# piHatJoystick.net
KiCad netlist of a schematic drawn in EAGLE
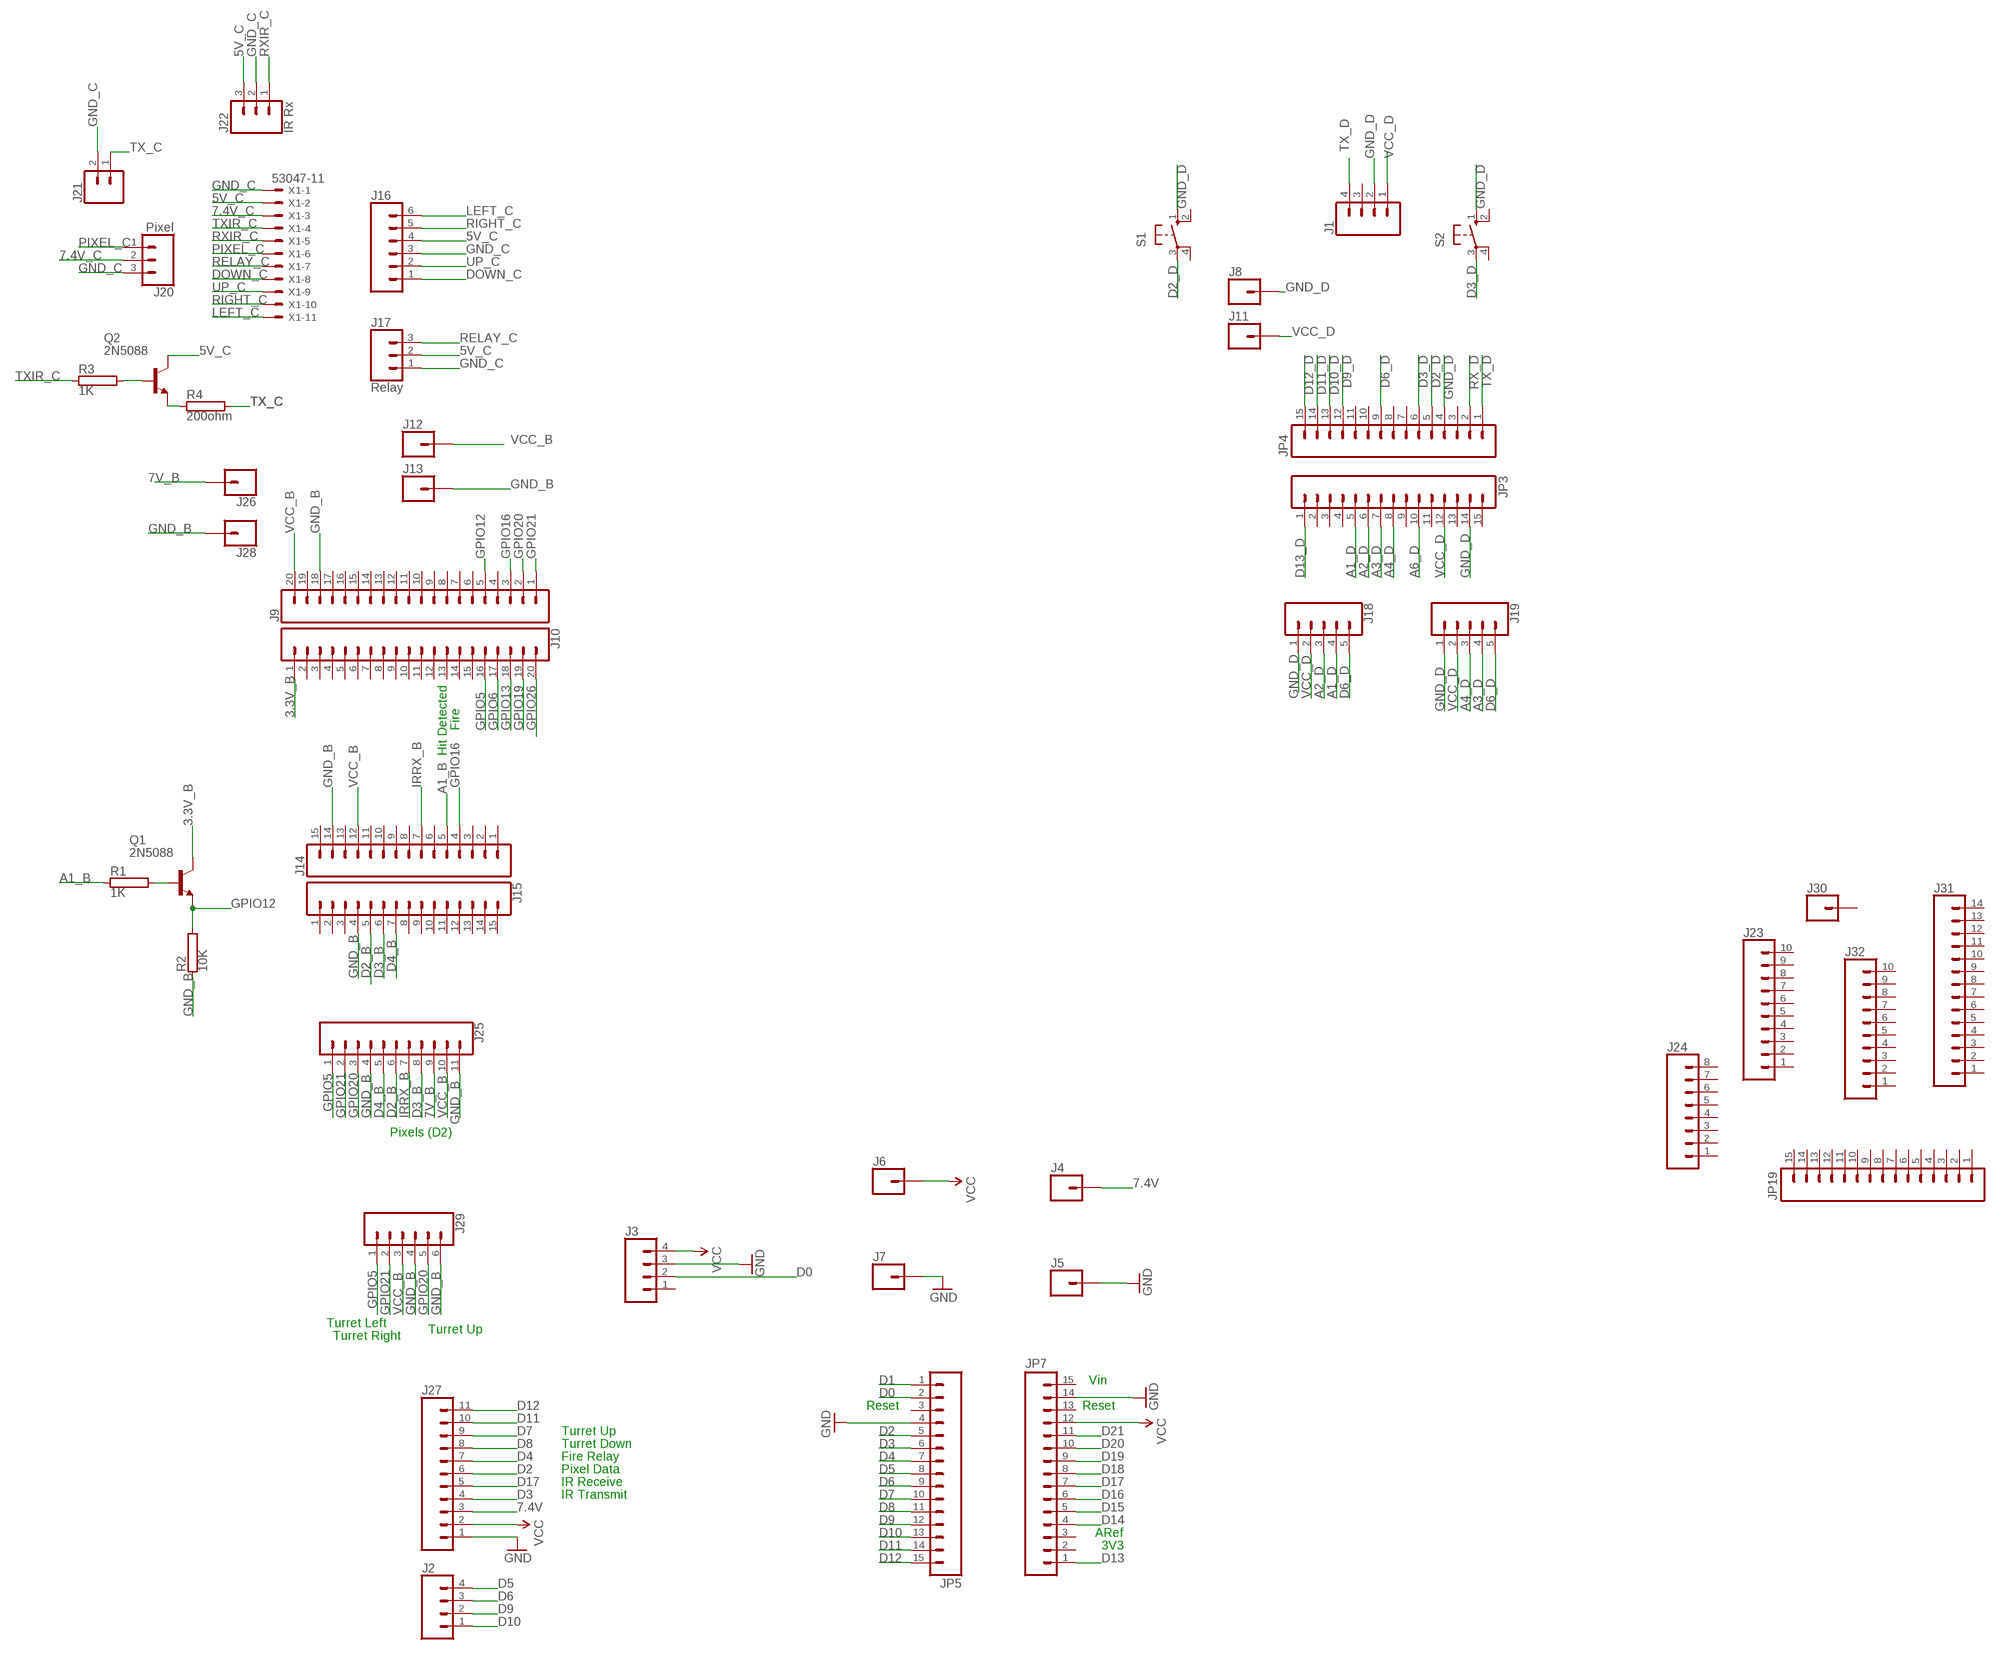
[diagram p0: schematic, sheet 1]

(export (version "E")
  (design (tool "Eeschema 10.0.6"))
  (components
    (comp (ref "J1")
      (value "CONN_04")
      (footprint "eagle-import:1X04")
      (libsource (lib "eagle-import") (part "SparkFun-Connectors_513_CONN_04"))
    )
    (comp (ref "J2")
      (value "CONN_04")
      (footprint "eagle-import:1X04")
      (libsource (lib "eagle-import") (part "CONN_04"))
    )
    (comp (ref "J3")
      (value "CONN_04")
      (footprint "eagle-import:1X04")
      (libsource (lib "eagle-import") (part "CONN_04"))
    )
    (comp (ref "J4")
      (value "CONN_01")
      (footprint "eagle-import:1X01")
      (libsource (lib "eagle-import") (part "SparkFun-Connectors_513_CONN_01"))
    )
    (comp (ref "J5")
      (value "CONN_01")
      (footprint "eagle-import:1X01")
      (libsource (lib "eagle-import") (part "SparkFun-Connectors_513_CONN_01"))
    )
    (comp (ref "J6")
      (value "CONN_01")
      (footprint "eagle-import:1X01")
      (libsource (lib "eagle-import") (part "SparkFun-Connectors_513_CONN_01"))
    )
    (comp (ref "J7")
      (value "CONN_01")
      (footprint "eagle-import:1X01")
      (libsource (lib "eagle-import") (part "SparkFun-Connectors_513_CONN_01"))
    )
    (comp (ref "J8")
      (value "CONN_01")
      (footprint "eagle-import:1X01")
      (libsource (lib "eagle-import") (part "SparkFun-Connectors_513_CONN_01"))
    )
    (comp (ref "J9")
      (value "CONN_20")
      (footprint "eagle-import:1X20")
      (libsource (lib "eagle-import") (part "CONN_20"))
    )
    (comp (ref "J10")
      (value "CONN_20")
      (footprint "eagle-import:1X20")
      (libsource (lib "eagle-import") (part "CONN_20"))
    )
    (comp (ref "J11")
      (value "CONN_01")
      (footprint "eagle-import:1X01")
      (libsource (lib "eagle-import") (part "SparkFun-Connectors_513_CONN_01"))
    )
    (comp (ref "J12")
      (value "CONN_01")
      (footprint "eagle-import:1X01")
      (libsource (lib "eagle-import") (part "CONN_01"))
    )
    (comp (ref "J13")
      (value "CONN_01")
      (footprint "eagle-import:1X01")
      (libsource (lib "eagle-import") (part "CONN_01"))
    )
    (comp (ref "J14")
      (value "CONN_15")
      (footprint "eagle-import:1X15")
      (libsource (lib "eagle-import") (part "CONN_15"))
    )
    (comp (ref "J15")
      (value "CONN_15")
      (footprint "eagle-import:1X15")
      (libsource (lib "eagle-import") (part "CONN_15"))
    )
    (comp (ref "J16")
      (value "CONN_06NO_SILK_FEMALE_PTH")
      (footprint "eagle-import:1X06_NO_SILK")
      (libsource (lib "eagle-import") (part "CONN_06NO_SILK_FEMALE_PTH"))
    )
    (comp (ref "J17")
      (value "Relay")
      (footprint "eagle-import:1X03")
      (libsource (lib "eagle-import") (part "CONN_03"))
    )
    (comp (ref "J18")
      (value "CONN_05")
      (footprint "eagle-import:1X05")
      (libsource (lib "eagle-import") (part "CONN_05"))
    )
    (comp (ref "J19")
      (value "CONN_05")
      (footprint "eagle-import:1X05")
      (libsource (lib "eagle-import") (part "CONN_05"))
    )
    (comp (ref "J20")
      (value "Pixel")
      (footprint "eagle-import:1X03")
      (libsource (lib "eagle-import") (part "CONN_03"))
    )
    (comp (ref "J21")
      (value "CONN_02")
      (footprint "eagle-import:1X02")
      (libsource (lib "eagle-import") (part "CONN_02"))
    )
    (comp (ref "J22")
      (value "IR Rx")
      (footprint "eagle-import:1X03")
      (libsource (lib "eagle-import") (part "CONN_03"))
    )
    (comp (ref "J23")
      (value "CONN_10\"")
      (footprint "eagle-import:1X10")
      (libsource (lib "eagle-import") (part "CONN_10{dblquote}"))
    )
    (comp (ref "J24")
      (value "CONN_08\"")
      (footprint "eagle-import:1X08")
      (libsource (lib "eagle-import") (part "CONN_08{dblquote}"))
    )
    (comp (ref "J25")
      (value "CONN_11")
      (footprint "eagle-import:1X11")
      (libsource (lib "eagle-import") (part "CONN_11"))
    )
    (comp (ref "J26")
      (value "CONN_01")
      (footprint "eagle-import:1X01")
      (libsource (lib "eagle-import") (part "CONN_01"))
    )
    (comp (ref "J27")
      (value "CONN_11")
      (footprint "eagle-import:1X11")
      (libsource (lib "eagle-import") (part "SparkFun-Connectors_513_CONN_11"))
    )
    (comp (ref "J28")
      (value "CONN_01")
      (footprint "eagle-import:1X01")
      (libsource (lib "eagle-import") (part "CONN_01"))
    )
    (comp (ref "J29")
      (value "CONN_06NO_SILK_FEMALE_PTH")
      (footprint "eagle-import:1X06_NO_SILK")
      (libsource (lib "eagle-import") (part "CONN_06NO_SILK_FEMALE_PTH"))
    )
    (comp (ref "J30")
      (value "CONN_01")
      (footprint "eagle-import:1X01")
      (libsource (lib "eagle-import") (part "SparkFun-Connectors_513_CONN_01"))
    )
    (comp (ref "J31")
      (value "CONN_14")
      (footprint "eagle-import:1X14")
      (libsource (lib "eagle-import") (part "CONN_14"))
    )
    (comp (ref "J32")
      (value "CONN_10\"")
      (footprint "eagle-import:1X10")
      (libsource (lib "eagle-import") (part "CONN_10{dblquote}"))
    )
    (comp (ref "JP3")
      (value "M15")
      (footprint "eagle-import:1X15@1")
      (libsource (lib "eagle-import") (part "M15"))
    )
    (comp (ref "JP4")
      (value "M15")
      (footprint "eagle-import:1X15@1")
      (libsource (lib "eagle-import") (part "M15"))
    )
    (comp (ref "JP5")
      (value "M15")
      (footprint "eagle-import:1X15@1")
      (libsource (lib "eagle-import") (part "M15"))
    )
    (comp (ref "JP7")
      (value "M15")
      (footprint "eagle-import:1X15@1")
      (libsource (lib "eagle-import") (part "M15"))
    )
    (comp (ref "JP19")
      (value "M15")
      (footprint "eagle-import:1X15@1")
      (libsource (lib "eagle-import") (part "M15"))
    )
    (comp (ref "Q1")
      (value "2N5088")
      (footprint "eagle-import:TO92")
      (libsource (lib "eagle-import") (part "2N5088"))
    )
    (comp (ref "Q2")
      (value "2N5088")
      (footprint "eagle-import:TO92")
      (libsource (lib "eagle-import") (part "2N5088"))
    )
    (comp (ref "R1")
      (value "1K")
      (footprint "eagle-import:CA0001")
      (libsource (lib "eagle-import") (part "RCA0001"))
    )
    (comp (ref "R2")
      (value "10K")
      (footprint "eagle-import:CA0001")
      (libsource (lib "eagle-import") (part "RCA0001"))
    )
    (comp (ref "R3")
      (value "1K")
      (footprint "eagle-import:CA0001")
      (libsource (lib "eagle-import") (part "RCA0001"))
    )
    (comp (ref "R4")
      (value "200ohm")
      (footprint "eagle-import:CA0001")
      (libsource (lib "eagle-import") (part "RCA0001"))
    )
    (comp (ref "S1")
      (value "40-XX")
      (footprint "eagle-import:B3F-40XX")
      (fields (field (name "MF") "OMRON COMPONENTS USA") (field (name "MPN") "B3F-4000"))
      (libsource (lib "eagle-import") (part "40-XX"))
    )
    (comp (ref "S2")
      (value "40-XX")
      (footprint "eagle-import:B3F-40XX")
      (fields (field (name "MF") "OMRON COMPONENTS USA") (field (name "MPN") "B3F-4000"))
      (libsource (lib "eagle-import") (part "40-XX"))
    )
    (comp (ref "X1")
      (value "53047-11")
      (footprint "eagle-import:53047-11")
      (fields (field (name "MF") "WALDOM/MOLEX") (field (name "MPN") "53047-1110"))
      (libsource (lib "eagle-import") (part "53?-11047"))
    )
  )
  (nets
    (net (code "1") (name "/3.3V_B") (class "Default")
      (node (ref "J10") (pin "1") (pinfunction "1_1") (pintype "passive"))
      (node (ref "Q1") (pin "1") (pinfunction "C_1") (pintype "passive"))
    )
    (net (code "2") (name "/5V_C") (class "Default")
      (node (ref "J16") (pin "4") (pinfunction "4_4") (pintype "passive"))
      (node (ref "J17") (pin "2") (pinfunction "2_2") (pintype "passive"))
      (node (ref "J22") (pin "3") (pinfunction "3_3") (pintype "passive"))
      (node (ref "Q2") (pin "1") (pinfunction "C_1") (pintype "passive"))
      (node (ref "X1") (pin "2") (pinfunction "S_2") (pintype "passive"))
    )
    (net (code "3") (name "/7.4V") (class "Default")
      (node (ref "J27") (pin "3") (pinfunction "3_3") (pintype "passive"))
      (node (ref "J4") (pin "1") (pinfunction "1_1") (pintype "passive"))
    )
    (net (code "4") (name "/7.4V_C") (class "Default")
      (node (ref "J20") (pin "2") (pinfunction "2_2") (pintype "passive"))
      (node (ref "X1") (pin "3") (pinfunction "S_3") (pintype "passive"))
    )
    (net (code "5") (name "/7V_B") (class "Default")
      (node (ref "J25") (pin "9") (pinfunction "9_9") (pintype "passive"))
      (node (ref "J26") (pin "1") (pinfunction "1_1") (pintype "passive"))
    )
    (net (code "6") (name "/A1_B") (class "Default")
      (node (ref "J14") (pin "5") (pinfunction "5_5") (pintype "passive"))
      (node (ref "R1") (pin "1") (pinfunction "1_1") (pintype "passive"))
    )
    (net (code "7") (name "/A1_D") (class "Default")
      (node (ref "J18") (pin "4") (pinfunction "4_4") (pintype "passive"))
      (node (ref "JP3") (pin "5") (pinfunction "5_5") (pintype "passive"))
    )
    (net (code "8") (name "/A2_D") (class "Default")
      (node (ref "J18") (pin "3") (pinfunction "3_3") (pintype "passive"))
      (node (ref "JP3") (pin "6") (pinfunction "6_6") (pintype "passive"))
    )
    (net (code "9") (name "/A3_D") (class "Default")
      (node (ref "J19") (pin "4") (pinfunction "4_4") (pintype "passive"))
      (node (ref "JP3") (pin "7") (pinfunction "7_7") (pintype "passive"))
    )
    (net (code "10") (name "/A4_D") (class "Default")
      (node (ref "J19") (pin "3") (pinfunction "3_3") (pintype "passive"))
      (node (ref "JP3") (pin "8") (pinfunction "8_8") (pintype "passive"))
    )
    (net (code "11") (name "/A6_D") (class "Default")
      (node (ref "JP3") (pin "10") (pinfunction "10_10") (pintype "passive"))
    )
    (net (code "12") (name "/D0") (class "Default")
      (node (ref "J3") (pin "2") (pinfunction "2_2") (pintype "passive"))
      (node (ref "JP5") (pin "2") (pinfunction "2_2") (pintype "passive"))
    )
    (net (code "13") (name "/D1") (class "Default")
      (node (ref "JP5") (pin "1") (pinfunction "1_1") (pintype "passive"))
    )
    (net (code "14") (name "/D2") (class "Default")
      (node (ref "J27") (pin "6") (pinfunction "6_6") (pintype "passive"))
      (node (ref "JP5") (pin "5") (pinfunction "5_5") (pintype "passive"))
    )
    (net (code "15") (name "/D2_B") (class "Default")
      (node (ref "J15") (pin "5") (pinfunction "5_5") (pintype "passive"))
      (node (ref "J25") (pin "6") (pinfunction "6_6") (pintype "passive"))
    )
    (net (code "16") (name "/D2_D") (class "Default")
      (node (ref "JP4") (pin "5") (pinfunction "5_5") (pintype "passive"))
      (node (ref "S1") (pin "3") (pinfunction "P_3") (pintype "passive"))
    )
    (net (code "17") (name "/D3") (class "Default")
      (node (ref "J27") (pin "4") (pinfunction "4_4") (pintype "passive"))
      (node (ref "JP5") (pin "6") (pinfunction "6_6") (pintype "passive"))
    )
    (net (code "18") (name "/D3_B") (class "Default")
      (node (ref "J15") (pin "6") (pinfunction "6_6") (pintype "passive"))
      (node (ref "J25") (pin "8") (pinfunction "8_8") (pintype "passive"))
    )
    (net (code "19") (name "/D3_D") (class "Default")
      (node (ref "JP4") (pin "6") (pinfunction "6_6") (pintype "passive"))
      (node (ref "S2") (pin "3") (pinfunction "P_3") (pintype "passive"))
    )
    (net (code "20") (name "/D4") (class "Default")
      (node (ref "J27") (pin "7") (pinfunction "7_7") (pintype "passive"))
      (node (ref "JP5") (pin "7") (pinfunction "7_7") (pintype "passive"))
    )
    (net (code "21") (name "/D4_B") (class "Default")
      (node (ref "J15") (pin "7") (pinfunction "7_7") (pintype "passive"))
      (node (ref "J25") (pin "5") (pinfunction "5_5") (pintype "passive"))
    )
    (net (code "22") (name "/D5") (class "Default")
      (node (ref "J2") (pin "4") (pinfunction "4_4") (pintype "passive"))
      (node (ref "JP5") (pin "8") (pinfunction "8_8") (pintype "passive"))
    )
    (net (code "23") (name "/D6") (class "Default")
      (node (ref "J2") (pin "3") (pinfunction "3_3") (pintype "passive"))
      (node (ref "JP5") (pin "9") (pinfunction "9_9") (pintype "passive"))
    )
    (net (code "24") (name "/D6_D") (class "Default")
      (node (ref "J18") (pin "5") (pinfunction "5_5") (pintype "passive"))
      (node (ref "J19") (pin "5") (pinfunction "5_5") (pintype "passive"))
      (node (ref "JP4") (pin "9") (pinfunction "9_9") (pintype "passive"))
    )
    (net (code "25") (name "/D7") (class "Default")
      (node (ref "J27") (pin "9") (pinfunction "9_9") (pintype "passive"))
      (node (ref "JP5") (pin "10") (pinfunction "10_10") (pintype "passive"))
    )
    (net (code "26") (name "/D8") (class "Default")
      (node (ref "J27") (pin "8") (pinfunction "8_8") (pintype "passive"))
      (node (ref "JP5") (pin "11") (pinfunction "11_11") (pintype "passive"))
    )
    (net (code "27") (name "/D9") (class "Default")
      (node (ref "J2") (pin "2") (pinfunction "2_2") (pintype "passive"))
      (node (ref "JP5") (pin "12") (pinfunction "12_12") (pintype "passive"))
    )
    (net (code "28") (name "/D9_D") (class "Default")
      (node (ref "JP4") (pin "12") (pinfunction "12_12") (pintype "passive"))
    )
    (net (code "29") (name "/D10") (class "Default")
      (node (ref "J2") (pin "1") (pinfunction "1_1") (pintype "passive"))
      (node (ref "JP5") (pin "13") (pinfunction "13_13") (pintype "passive"))
    )
    (net (code "30") (name "/D10_D") (class "Default")
      (node (ref "JP4") (pin "13") (pinfunction "13_13") (pintype "passive"))
    )
    (net (code "31") (name "/D11") (class "Default")
      (node (ref "J27") (pin "10") (pinfunction "10_10") (pintype "passive"))
      (node (ref "JP5") (pin "14") (pinfunction "14_14") (pintype "passive"))
    )
    (net (code "32") (name "/D11_D") (class "Default")
      (node (ref "JP4") (pin "14") (pinfunction "14_14") (pintype "passive"))
    )
    (net (code "33") (name "/D12") (class "Default")
      (node (ref "J27") (pin "11") (pinfunction "11_11") (pintype "passive"))
      (node (ref "JP5") (pin "15") (pinfunction "15_15") (pintype "passive"))
    )
    (net (code "34") (name "/D12_D") (class "Default")
      (node (ref "JP4") (pin "15") (pinfunction "15_15") (pintype "passive"))
    )
    (net (code "35") (name "/D13") (class "Default")
      (node (ref "JP7") (pin "1") (pinfunction "1_1") (pintype "passive"))
    )
    (net (code "36") (name "/D13_D") (class "Default")
      (node (ref "JP3") (pin "1") (pinfunction "1_1") (pintype "passive"))
    )
    (net (code "37") (name "/D14") (class "Default")
      (node (ref "JP7") (pin "4") (pinfunction "4_4") (pintype "passive"))
    )
    (net (code "38") (name "/D15") (class "Default")
      (node (ref "JP7") (pin "5") (pinfunction "5_5") (pintype "passive"))
    )
    (net (code "39") (name "/D16") (class "Default")
      (node (ref "JP7") (pin "6") (pinfunction "6_6") (pintype "passive"))
    )
    (net (code "40") (name "/D17") (class "Default")
      (node (ref "J27") (pin "5") (pinfunction "5_5") (pintype "passive"))
      (node (ref "JP7") (pin "7") (pinfunction "7_7") (pintype "passive"))
    )
    (net (code "41") (name "/D18") (class "Default")
      (node (ref "JP7") (pin "8") (pinfunction "8_8") (pintype "passive"))
    )
    (net (code "42") (name "/D19") (class "Default")
      (node (ref "JP7") (pin "9") (pinfunction "9_9") (pintype "passive"))
    )
    (net (code "43") (name "/D20") (class "Default")
      (node (ref "JP7") (pin "10") (pinfunction "10_10") (pintype "passive"))
    )
    (net (code "44") (name "/D21") (class "Default")
      (node (ref "JP7") (pin "11") (pinfunction "11_11") (pintype "passive"))
    )
    (net (code "45") (name "/DOWN_C") (class "Default")
      (node (ref "J16") (pin "1") (pinfunction "1_1") (pintype "passive"))
      (node (ref "X1") (pin "8") (pinfunction "S_8") (pintype "passive"))
    )
    (net (code "46") (name "/GND_B") (class "Default")
      (node (ref "J13") (pin "1") (pinfunction "1_1") (pintype "passive"))
      (node (ref "J14") (pin "14") (pinfunction "14_14") (pintype "passive"))
      (node (ref "J15") (pin "4") (pinfunction "4_4") (pintype "passive"))
      (node (ref "J25") (pin "11") (pinfunction "11_11") (pintype "passive"))
      (node (ref "J25") (pin "4") (pinfunction "4_4") (pintype "passive"))
      (node (ref "J28") (pin "1") (pinfunction "1_1") (pintype "passive"))
      (node (ref "J29") (pin "4") (pinfunction "4_4") (pintype "passive"))
      (node (ref "J29") (pin "6") (pinfunction "6_6") (pintype "passive"))
      (node (ref "J9") (pin "18") (pinfunction "18_18") (pintype "passive"))
      (node (ref "R2") (pin "1") (pinfunction "1_1") (pintype "passive"))
    )
    (net (code "47") (name "/GND_C") (class "Default")
      (node (ref "J16") (pin "3") (pinfunction "3_3") (pintype "passive"))
      (node (ref "J17") (pin "1") (pinfunction "1_1") (pintype "passive"))
      (node (ref "J20") (pin "3") (pinfunction "3_3") (pintype "passive"))
      (node (ref "J21") (pin "2") (pinfunction "2_2") (pintype "passive"))
      (node (ref "J22") (pin "2") (pinfunction "2_2") (pintype "passive"))
      (node (ref "X1") (pin "1") (pinfunction "S_1") (pintype "passive"))
    )
    (net (code "48") (name "/GND_D") (class "Default")
      (node (ref "J1") (pin "2") (pinfunction "2_2") (pintype "passive"))
      (node (ref "J18") (pin "1") (pinfunction "1_1") (pintype "passive"))
      (node (ref "J19") (pin "1") (pinfunction "1_1") (pintype "passive"))
      (node (ref "J8") (pin "1") (pinfunction "1_1") (pintype "passive"))
      (node (ref "JP3") (pin "14") (pinfunction "14_14") (pintype "passive"))
      (node (ref "JP4") (pin "4") (pinfunction "4_4") (pintype "passive"))
      (node (ref "S1") (pin "1") (pinfunction "S_1") (pintype "passive"))
      (node (ref "S2") (pin "1") (pinfunction "S_1") (pintype "passive"))
    )
    (net (code "49") (name "/GPIO5") (class "Default")
      (node (ref "J10") (pin "16") (pinfunction "16_16") (pintype "passive"))
      (node (ref "J25") (pin "1") (pinfunction "1_1") (pintype "passive"))
      (node (ref "J29") (pin "1") (pinfunction "1_1") (pintype "passive"))
    )
    (net (code "50") (name "/GPIO6") (class "Default")
      (node (ref "J10") (pin "17") (pinfunction "17_17") (pintype "passive"))
    )
    (net (code "51") (name "/GPIO12") (class "Default")
      (node (ref "J9") (pin "5") (pinfunction "5_5") (pintype "passive"))
      (node (ref "Q1") (pin "3") (pinfunction "E_3") (pintype "passive"))
      (node (ref "R2") (pin "2") (pinfunction "2_2") (pintype "passive"))
    )
    (net (code "52") (name "/GPIO13") (class "Default")
      (node (ref "J10") (pin "18") (pinfunction "18_18") (pintype "passive"))
    )
    (net (code "53") (name "/GPIO16") (class "Default")
      (node (ref "J14") (pin "4") (pinfunction "4_4") (pintype "passive"))
      (node (ref "J9") (pin "3") (pinfunction "3_3") (pintype "passive"))
    )
    (net (code "54") (name "/GPIO19") (class "Default")
      (node (ref "J10") (pin "19") (pinfunction "19_19") (pintype "passive"))
    )
    (net (code "55") (name "/GPIO20") (class "Default")
      (node (ref "J25") (pin "3") (pinfunction "3_3") (pintype "passive"))
      (node (ref "J29") (pin "5") (pinfunction "5_5") (pintype "passive"))
      (node (ref "J9") (pin "2") (pinfunction "2_2") (pintype "passive"))
    )
    (net (code "56") (name "/GPIO21") (class "Default")
      (node (ref "J25") (pin "2") (pinfunction "2_2") (pintype "passive"))
      (node (ref "J29") (pin "2") (pinfunction "2_2") (pintype "passive"))
      (node (ref "J9") (pin "1") (pinfunction "1_1") (pintype "passive"))
    )
    (net (code "57") (name "/GPIO26") (class "Default")
      (node (ref "J10") (pin "20") (pinfunction "20_20") (pintype "passive"))
    )
    (net (code "58") (name "/IRRX_B") (class "Default")
      (node (ref "J14") (pin "7") (pinfunction "7_7") (pintype "passive"))
      (node (ref "J25") (pin "7") (pinfunction "7_7") (pintype "passive"))
    )
    (net (code "59") (name "/LEFT_C") (class "Default")
      (node (ref "J16") (pin "6") (pinfunction "6_6") (pintype "passive"))
      (node (ref "X1") (pin "11") (pinfunction "S_11") (pintype "passive"))
    )
    (net (code "60") (name "/PIXEL_C") (class "Default")
      (node (ref "J20") (pin "1") (pinfunction "1_1") (pintype "passive"))
      (node (ref "X1") (pin "6") (pinfunction "S_6") (pintype "passive"))
    )
    (net (code "61") (name "/RELAY_C") (class "Default")
      (node (ref "J17") (pin "3") (pinfunction "3_3") (pintype "passive"))
      (node (ref "X1") (pin "7") (pinfunction "S_7") (pintype "passive"))
    )
    (net (code "62") (name "/RIGHT_C") (class "Default")
      (node (ref "J16") (pin "5") (pinfunction "5_5") (pintype "passive"))
      (node (ref "X1") (pin "10") (pinfunction "S_10") (pintype "passive"))
    )
    (net (code "63") (name "/RXIR_C") (class "Default")
      (node (ref "J22") (pin "1") (pinfunction "1_1") (pintype "passive"))
      (node (ref "X1") (pin "5") (pinfunction "S_5") (pintype "passive"))
    )
    (net (code "64") (name "/RX_D") (class "Default")
      (node (ref "JP4") (pin "2") (pinfunction "2_2") (pintype "passive"))
    )
    (net (code "65") (name "/TXIR_C") (class "Default")
      (node (ref "R3") (pin "1") (pinfunction "1_1") (pintype "passive"))
      (node (ref "X1") (pin "4") (pinfunction "S_4") (pintype "passive"))
    )
    (net (code "66") (name "/TX_C") (class "Default")
      (node (ref "J21") (pin "1") (pinfunction "1_1") (pintype "passive"))
      (node (ref "R4") (pin "2") (pinfunction "2_2") (pintype "passive"))
    )
    (net (code "67") (name "/TX_D") (class "Default")
      (node (ref "J1") (pin "4") (pinfunction "4_4") (pintype "passive"))
      (node (ref "JP4") (pin "1") (pinfunction "1_1") (pintype "passive"))
    )
    (net (code "68") (name "/UP_C") (class "Default")
      (node (ref "J16") (pin "2") (pinfunction "2_2") (pintype "passive"))
      (node (ref "X1") (pin "9") (pinfunction "S_9") (pintype "passive"))
    )
    (net (code "69") (name "/VCC_B") (class "Default")
      (node (ref "J12") (pin "1") (pinfunction "1_1") (pintype "passive"))
      (node (ref "J14") (pin "12") (pinfunction "12_12") (pintype "passive"))
      (node (ref "J25") (pin "10") (pinfunction "10_10") (pintype "passive"))
      (node (ref "J29") (pin "3") (pinfunction "3_3") (pintype "passive"))
      (node (ref "J9") (pin "20") (pinfunction "20_20") (pintype "passive"))
    )
    (net (code "70") (name "/VCC_D") (class "Default")
      (node (ref "J1") (pin "1") (pinfunction "1_1") (pintype "passive"))
      (node (ref "J11") (pin "1") (pinfunction "1_1") (pintype "passive"))
      (node (ref "J18") (pin "2") (pinfunction "2_2") (pintype "passive"))
      (node (ref "J19") (pin "2") (pinfunction "2_2") (pintype "passive"))
      (node (ref "JP3") (pin "12") (pinfunction "12_12") (pintype "passive"))
    )
    (net (code "71") (name "GND") (class "Default")
      (node (ref "J27") (pin "1") (pinfunction "1_1") (pintype "passive"))
      (node (ref "J3") (pin "3") (pinfunction "3_3") (pintype "passive"))
      (node (ref "J5") (pin "1") (pinfunction "1_1") (pintype "passive"))
      (node (ref "J7") (pin "1") (pinfunction "1_1") (pintype "passive"))
      (node (ref "JP5") (pin "4") (pinfunction "4_4") (pintype "passive"))
      (node (ref "JP7") (pin "14") (pinfunction "14_14") (pintype "passive"))
    )
    (net (code "72") (name "Net-(Q1-B)") (class "Default")
      (node (ref "Q1") (pin "2") (pinfunction "B_2") (pintype "passive"))
      (node (ref "R1") (pin "2") (pinfunction "2_2") (pintype "passive"))
    )
    (net (code "73") (name "Net-(Q2-B)") (class "Default")
      (node (ref "Q2") (pin "2") (pinfunction "B_2") (pintype "passive"))
      (node (ref "R3") (pin "2") (pinfunction "2_2") (pintype "passive"))
    )
    (net (code "74") (name "Net-(Q2-E)") (class "Default")
      (node (ref "Q2") (pin "3") (pinfunction "E_3") (pintype "passive"))
      (node (ref "R4") (pin "1") (pinfunction "1_1") (pintype "passive"))
    )
    (net (code "75") (name "VCC") (class "Default")
      (node (ref "J27") (pin "2") (pinfunction "2_2") (pintype "passive"))
      (node (ref "J3") (pin "4") (pinfunction "4_4") (pintype "passive"))
      (node (ref "J6") (pin "1") (pinfunction "1_1") (pintype "passive"))
      (node (ref "JP7") (pin "12") (pinfunction "12_12") (pintype "passive"))
    )
    (net (code "76") (name "unconnected-(J1-Pad3)") (class "Default")
      (node (ref "J1") (pin "3") (pinfunction "3_3") (pintype "passive"))
    )
    (net (code "77") (name "unconnected-(J3-Pad1)") (class "Default")
      (node (ref "J3") (pin "1") (pinfunction "1_1") (pintype "passive"))
    )
    (net (code "78") (name "unconnected-(J9-Pad4)") (class "Default")
      (node (ref "J9") (pin "4") (pinfunction "4_4") (pintype "passive"))
    )
    (net (code "79") (name "unconnected-(J9-Pad6)") (class "Default")
      (node (ref "J9") (pin "6") (pinfunction "6_6") (pintype "passive"))
    )
    (net (code "80") (name "unconnected-(J9-Pad7)") (class "Default")
      (node (ref "J9") (pin "7") (pinfunction "7_7") (pintype "passive"))
    )
    (net (code "81") (name "unconnected-(J9-Pad8)") (class "Default")
      (node (ref "J9") (pin "8") (pinfunction "8_8") (pintype "passive"))
    )
    (net (code "82") (name "unconnected-(J9-Pad9)") (class "Default")
      (node (ref "J9") (pin "9") (pinfunction "9_9") (pintype "passive"))
    )
    (net (code "83") (name "unconnected-(J9-Pad10)") (class "Default")
      (node (ref "J9") (pin "10") (pinfunction "10_10") (pintype "passive"))
    )
    (net (code "84") (name "unconnected-(J9-Pad11)") (class "Default")
      (node (ref "J9") (pin "11") (pinfunction "11_11") (pintype "passive"))
    )
    (net (code "85") (name "unconnected-(J9-Pad12)") (class "Default")
      (node (ref "J9") (pin "12") (pinfunction "12_12") (pintype "passive"))
    )
    (net (code "86") (name "unconnected-(J9-Pad13)") (class "Default")
      (node (ref "J9") (pin "13") (pinfunction "13_13") (pintype "passive"))
    )
    (net (code "87") (name "unconnected-(J9-Pad14)") (class "Default")
      (node (ref "J9") (pin "14") (pinfunction "14_14") (pintype "passive"))
    )
    (net (code "88") (name "unconnected-(J9-Pad15)") (class "Default")
      (node (ref "J9") (pin "15") (pinfunction "15_15") (pintype "passive"))
    )
    (net (code "89") (name "unconnected-(J9-Pad16)") (class "Default")
      (node (ref "J9") (pin "16") (pinfunction "16_16") (pintype "passive"))
    )
    (net (code "90") (name "unconnected-(J9-Pad17)") (class "Default")
      (node (ref "J9") (pin "17") (pinfunction "17_17") (pintype "passive"))
    )
    (net (code "91") (name "unconnected-(J9-Pad19)") (class "Default")
      (node (ref "J9") (pin "19") (pinfunction "19_19") (pintype "passive"))
    )
    (net (code "92") (name "unconnected-(J10-Pad2)") (class "Default")
      (node (ref "J10") (pin "2") (pinfunction "2_2") (pintype "passive"))
    )
    (net (code "93") (name "unconnected-(J10-Pad3)") (class "Default")
      (node (ref "J10") (pin "3") (pinfunction "3_3") (pintype "passive"))
    )
    (net (code "94") (name "unconnected-(J10-Pad4)") (class "Default")
      (node (ref "J10") (pin "4") (pinfunction "4_4") (pintype "passive"))
    )
    (net (code "95") (name "unconnected-(J10-Pad5)") (class "Default")
      (node (ref "J10") (pin "5") (pinfunction "5_5") (pintype "passive"))
    )
    (net (code "96") (name "unconnected-(J10-Pad6)") (class "Default")
      (node (ref "J10") (pin "6") (pinfunction "6_6") (pintype "passive"))
    )
    (net (code "97") (name "unconnected-(J10-Pad7)") (class "Default")
      (node (ref "J10") (pin "7") (pinfunction "7_7") (pintype "passive"))
    )
    (net (code "98") (name "unconnected-(J10-Pad8)") (class "Default")
      (node (ref "J10") (pin "8") (pinfunction "8_8") (pintype "passive"))
    )
    (net (code "99") (name "unconnected-(J10-Pad9)") (class "Default")
      (node (ref "J10") (pin "9") (pinfunction "9_9") (pintype "passive"))
    )
    (net (code "100") (name "unconnected-(J10-Pad10)") (class "Default")
      (node (ref "J10") (pin "10") (pinfunction "10_10") (pintype "passive"))
    )
    (net (code "101") (name "unconnected-(J10-Pad11)") (class "Default")
      (node (ref "J10") (pin "11") (pinfunction "11_11") (pintype "passive"))
    )
    (net (code "102") (name "unconnected-(J10-Pad12)") (class "Default")
      (node (ref "J10") (pin "12") (pinfunction "12_12") (pintype "passive"))
    )
    (net (code "103") (name "unconnected-(J10-Pad13)") (class "Default")
      (node (ref "J10") (pin "13") (pinfunction "13_13") (pintype "passive"))
    )
    (net (code "104") (name "unconnected-(J10-Pad14)") (class "Default")
      (node (ref "J10") (pin "14") (pinfunction "14_14") (pintype "passive"))
    )
    (net (code "105") (name "unconnected-(J10-Pad15)") (class "Default")
      (node (ref "J10") (pin "15") (pinfunction "15_15") (pintype "passive"))
    )
    (net (code "106") (name "unconnected-(J14-Pad1)") (class "Default")
      (node (ref "J14") (pin "1") (pinfunction "1_1") (pintype "passive"))
    )
    (net (code "107") (name "unconnected-(J14-Pad2)") (class "Default")
      (node (ref "J14") (pin "2") (pinfunction "2_2") (pintype "passive"))
    )
    (net (code "108") (name "unconnected-(J14-Pad3)") (class "Default")
      (node (ref "J14") (pin "3") (pinfunction "3_3") (pintype "passive"))
    )
    (net (code "109") (name "unconnected-(J14-Pad6)") (class "Default")
      (node (ref "J14") (pin "6") (pinfunction "6_6") (pintype "passive"))
    )
    (net (code "110") (name "unconnected-(J14-Pad8)") (class "Default")
      (node (ref "J14") (pin "8") (pinfunction "8_8") (pintype "passive"))
    )
    (net (code "111") (name "unconnected-(J14-Pad9)") (class "Default")
      (node (ref "J14") (pin "9") (pinfunction "9_9") (pintype "passive"))
    )
    (net (code "112") (name "unconnected-(J14-Pad10)") (class "Default")
      (node (ref "J14") (pin "10") (pinfunction "10_10") (pintype "passive"))
    )
    (net (code "113") (name "unconnected-(J14-Pad11)") (class "Default")
      (node (ref "J14") (pin "11") (pinfunction "11_11") (pintype "passive"))
    )
    (net (code "114") (name "unconnected-(J14-Pad13)") (class "Default")
      (node (ref "J14") (pin "13") (pinfunction "13_13") (pintype "passive"))
    )
    (net (code "115") (name "unconnected-(J14-Pad15)") (class "Default")
      (node (ref "J14") (pin "15") (pinfunction "15_15") (pintype "passive"))
    )
    (net (code "116") (name "unconnected-(J15-Pad1)") (class "Default")
      (node (ref "J15") (pin "1") (pinfunction "1_1") (pintype "passive"))
    )
    (net (code "117") (name "unconnected-(J15-Pad2)") (class "Default")
      (node (ref "J15") (pin "2") (pinfunction "2_2") (pintype "passive"))
    )
    (net (code "118") (name "unconnected-(J15-Pad3)") (class "Default")
      (node (ref "J15") (pin "3") (pinfunction "3_3") (pintype "passive"))
    )
    (net (code "119") (name "unconnected-(J15-Pad8)") (class "Default")
      (node (ref "J15") (pin "8") (pinfunction "8_8") (pintype "passive"))
    )
    (net (code "120") (name "unconnected-(J15-Pad9)") (class "Default")
      (node (ref "J15") (pin "9") (pinfunction "9_9") (pintype "passive"))
    )
    (net (code "121") (name "unconnected-(J15-Pad10)") (class "Default")
      (node (ref "J15") (pin "10") (pinfunction "10_10") (pintype "passive"))
    )
    (net (code "122") (name "unconnected-(J15-Pad11)") (class "Default")
      (node (ref "J15") (pin "11") (pinfunction "11_11") (pintype "passive"))
    )
    (net (code "123") (name "unconnected-(J15-Pad12)") (class "Default")
      (node (ref "J15") (pin "12") (pinfunction "12_12") (pintype "passive"))
    )
    (net (code "124") (name "unconnected-(J15-Pad13)") (class "Default")
      (node (ref "J15") (pin "13") (pinfunction "13_13") (pintype "passive"))
    )
    (net (code "125") (name "unconnected-(J15-Pad14)") (class "Default")
      (node (ref "J15") (pin "14") (pinfunction "14_14") (pintype "passive"))
    )
    (net (code "126") (name "unconnected-(J15-Pad15)") (class "Default")
      (node (ref "J15") (pin "15") (pinfunction "15_15") (pintype "passive"))
    )
    (net (code "127") (name "unconnected-(J23-Pad1)") (class "Default")
      (node (ref "J23") (pin "1") (pinfunction "1_1") (pintype "passive"))
    )
    (net (code "128") (name "unconnected-(J23-Pad2)") (class "Default")
      (node (ref "J23") (pin "2") (pinfunction "2_2") (pintype "passive"))
    )
    (net (code "129") (name "unconnected-(J23-Pad3)") (class "Default")
      (node (ref "J23") (pin "3") (pinfunction "3_3") (pintype "passive"))
    )
    (net (code "130") (name "unconnected-(J23-Pad4)") (class "Default")
      (node (ref "J23") (pin "4") (pinfunction "4_4") (pintype "passive"))
    )
    (net (code "131") (name "unconnected-(J23-Pad5)") (class "Default")
      (node (ref "J23") (pin "5") (pinfunction "5_5") (pintype "passive"))
    )
    (net (code "132") (name "unconnected-(J23-Pad6)") (class "Default")
      (node (ref "J23") (pin "6") (pinfunction "6_6") (pintype "passive"))
    )
    (net (code "133") (name "unconnected-(J23-Pad7)") (class "Default")
      (node (ref "J23") (pin "7") (pinfunction "7_7") (pintype "passive"))
    )
    (net (code "134") (name "unconnected-(J23-Pad8)") (class "Default")
      (node (ref "J23") (pin "8") (pinfunction "8_8") (pintype "passive"))
    )
    (net (code "135") (name "unconnected-(J23-Pad9)") (class "Default")
      (node (ref "J23") (pin "9") (pinfunction "9_9") (pintype "passive"))
    )
    (net (code "136") (name "unconnected-(J23-Pad10)") (class "Default")
      (node (ref "J23") (pin "10") (pinfunction "10_10") (pintype "passive"))
    )
    (net (code "137") (name "unconnected-(J24-Pad1)") (class "Default")
      (node (ref "J24") (pin "1") (pinfunction "1_1") (pintype "passive"))
    )
    (net (code "138") (name "unconnected-(J24-Pad2)") (class "Default")
      (node (ref "J24") (pin "2") (pinfunction "2_2") (pintype "passive"))
    )
    (net (code "139") (name "unconnected-(J24-Pad3)") (class "Default")
      (node (ref "J24") (pin "3") (pinfunction "3_3") (pintype "passive"))
    )
    (net (code "140") (name "unconnected-(J24-Pad4)") (class "Default")
      (node (ref "J24") (pin "4") (pinfunction "4_4") (pintype "passive"))
    )
    (net (code "141") (name "unconnected-(J24-Pad5)") (class "Default")
      (node (ref "J24") (pin "5") (pinfunction "5_5") (pintype "passive"))
    )
    (net (code "142") (name "unconnected-(J24-Pad6)") (class "Default")
      (node (ref "J24") (pin "6") (pinfunction "6_6") (pintype "passive"))
    )
    (net (code "143") (name "unconnected-(J24-Pad7)") (class "Default")
      (node (ref "J24") (pin "7") (pinfunction "7_7") (pintype "passive"))
    )
    (net (code "144") (name "unconnected-(J24-Pad8)") (class "Default")
      (node (ref "J24") (pin "8") (pinfunction "8_8") (pintype "passive"))
    )
    (net (code "145") (name "unconnected-(J30-Pad1)") (class "Default")
      (node (ref "J30") (pin "1") (pinfunction "1_1") (pintype "passive"))
    )
    (net (code "146") (name "unconnected-(J31-Pad1)") (class "Default")
      (node (ref "J31") (pin "1") (pinfunction "1_1") (pintype "passive"))
    )
    (net (code "147") (name "unconnected-(J31-Pad2)") (class "Default")
      (node (ref "J31") (pin "2") (pinfunction "2_2") (pintype "passive"))
    )
    (net (code "148") (name "unconnected-(J31-Pad3)") (class "Default")
      (node (ref "J31") (pin "3") (pinfunction "3_3") (pintype "passive"))
    )
    (net (code "149") (name "unconnected-(J31-Pad4)") (class "Default")
      (node (ref "J31") (pin "4") (pinfunction "4_4") (pintype "passive"))
    )
    (net (code "150") (name "unconnected-(J31-Pad5)") (class "Default")
      (node (ref "J31") (pin "5") (pinfunction "5_5") (pintype "passive"))
    )
    (net (code "151") (name "unconnected-(J31-Pad6)") (class "Default")
      (node (ref "J31") (pin "6") (pinfunction "6_6") (pintype "passive"))
    )
    (net (code "152") (name "unconnected-(J31-Pad7)") (class "Default")
      (node (ref "J31") (pin "7") (pinfunction "7_7") (pintype "passive"))
    )
    (net (code "153") (name "unconnected-(J31-Pad8)") (class "Default")
      (node (ref "J31") (pin "8") (pinfunction "8_8") (pintype "passive"))
    )
    (net (code "154") (name "unconnected-(J31-Pad9)") (class "Default")
      (node (ref "J31") (pin "9") (pinfunction "9_9") (pintype "passive"))
    )
    (net (code "155") (name "unconnected-(J31-Pad10)") (class "Default")
      (node (ref "J31") (pin "10") (pinfunction "10_10") (pintype "passive"))
    )
    (net (code "156") (name "unconnected-(J31-Pad11)") (class "Default")
      (node (ref "J31") (pin "11") (pinfunction "11_11") (pintype "passive"))
    )
    (net (code "157") (name "unconnected-(J31-Pad12)") (class "Default")
      (node (ref "J31") (pin "12") (pinfunction "12_12") (pintype "passive"))
    )
    (net (code "158") (name "unconnected-(J31-Pad13)") (class "Default")
      (node (ref "J31") (pin "13") (pinfunction "13_13") (pintype "passive"))
    )
    (net (code "159") (name "unconnected-(J31-Pad14)") (class "Default")
      (node (ref "J31") (pin "14") (pinfunction "14_14") (pintype "passive"))
    )
    (net (code "160") (name "unconnected-(J32-Pad1)") (class "Default")
      (node (ref "J32") (pin "1") (pinfunction "1_1") (pintype "passive"))
    )
    (net (code "161") (name "unconnected-(J32-Pad2)") (class "Default")
      (node (ref "J32") (pin "2") (pinfunction "2_2") (pintype "passive"))
    )
    (net (code "162") (name "unconnected-(J32-Pad3)") (class "Default")
      (node (ref "J32") (pin "3") (pinfunction "3_3") (pintype "passive"))
    )
    (net (code "163") (name "unconnected-(J32-Pad4)") (class "Default")
      (node (ref "J32") (pin "4") (pinfunction "4_4") (pintype "passive"))
    )
    (net (code "164") (name "unconnected-(J32-Pad5)") (class "Default")
      (node (ref "J32") (pin "5") (pinfunction "5_5") (pintype "passive"))
    )
    (net (code "165") (name "unconnected-(J32-Pad6)") (class "Default")
      (node (ref "J32") (pin "6") (pinfunction "6_6") (pintype "passive"))
    )
    (net (code "166") (name "unconnected-(J32-Pad7)") (class "Default")
      (node (ref "J32") (pin "7") (pinfunction "7_7") (pintype "passive"))
    )
    (net (code "167") (name "unconnected-(J32-Pad8)") (class "Default")
      (node (ref "J32") (pin "8") (pinfunction "8_8") (pintype "passive"))
    )
    (net (code "168") (name "unconnected-(J32-Pad9)") (class "Default")
      (node (ref "J32") (pin "9") (pinfunction "9_9") (pintype "passive"))
    )
    (net (code "169") (name "unconnected-(J32-Pad10)") (class "Default")
      (node (ref "J32") (pin "10") (pinfunction "10_10") (pintype "passive"))
    )
    (net (code "170") (name "unconnected-(JP3-Pad2)") (class "Default")
      (node (ref "JP3") (pin "2") (pinfunction "2_2") (pintype "passive"))
    )
    (net (code "171") (name "unconnected-(JP3-Pad3)") (class "Default")
      (node (ref "JP3") (pin "3") (pinfunction "3_3") (pintype "passive"))
    )
    (net (code "172") (name "unconnected-(JP3-Pad4)") (class "Default")
      (node (ref "JP3") (pin "4") (pinfunction "4_4") (pintype "passive"))
    )
    (net (code "173") (name "unconnected-(JP3-Pad9)") (class "Default")
      (node (ref "JP3") (pin "9") (pinfunction "9_9") (pintype "passive"))
    )
    (net (code "174") (name "unconnected-(JP3-Pad11)") (class "Default")
      (node (ref "JP3") (pin "11") (pinfunction "11_11") (pintype "passive"))
    )
    (net (code "175") (name "unconnected-(JP3-Pad13)") (class "Default")
      (node (ref "JP3") (pin "13") (pinfunction "13_13") (pintype "passive"))
    )
    (net (code "176") (name "unconnected-(JP3-Pad15)") (class "Default")
      (node (ref "JP3") (pin "15") (pinfunction "15_15") (pintype "passive"))
    )
    (net (code "177") (name "unconnected-(JP4-Pad3)") (class "Default")
      (node (ref "JP4") (pin "3") (pinfunction "3_3") (pintype "passive"))
    )
    (net (code "178") (name "unconnected-(JP4-Pad7)") (class "Default")
      (node (ref "JP4") (pin "7") (pinfunction "7_7") (pintype "passive"))
    )
    (net (code "179") (name "unconnected-(JP4-Pad8)") (class "Default")
      (node (ref "JP4") (pin "8") (pinfunction "8_8") (pintype "passive"))
    )
    (net (code "180") (name "unconnected-(JP4-Pad10)") (class "Default")
      (node (ref "JP4") (pin "10") (pinfunction "10_10") (pintype "passive"))
    )
    (net (code "181") (name "unconnected-(JP4-Pad11)") (class "Default")
      (node (ref "JP4") (pin "11") (pinfunction "11_11") (pintype "passive"))
    )
    (net (code "182") (name "unconnected-(JP5-Pad3)") (class "Default")
      (node (ref "JP5") (pin "3") (pinfunction "3_3") (pintype "passive"))
    )
    (net (code "183") (name "unconnected-(JP7-Pad2)") (class "Default")
      (node (ref "JP7") (pin "2") (pinfunction "2_2") (pintype "passive"))
    )
    (net (code "184") (name "unconnected-(JP7-Pad3)") (class "Default")
      (node (ref "JP7") (pin "3") (pinfunction "3_3") (pintype "passive"))
    )
    (net (code "185") (name "unconnected-(JP7-Pad13)") (class "Default")
      (node (ref "JP7") (pin "13") (pinfunction "13_13") (pintype "passive"))
    )
    (net (code "186") (name "unconnected-(JP7-Pad15)") (class "Default")
      (node (ref "JP7") (pin "15") (pinfunction "15_15") (pintype "passive"))
    )
    (net (code "187") (name "unconnected-(JP19-Pad1)") (class "Default")
      (node (ref "JP19") (pin "1") (pinfunction "1_1") (pintype "passive"))
    )
    (net (code "188") (name "unconnected-(JP19-Pad2)") (class "Default")
      (node (ref "JP19") (pin "2") (pinfunction "2_2") (pintype "passive"))
    )
    (net (code "189") (name "unconnected-(JP19-Pad3)") (class "Default")
      (node (ref "JP19") (pin "3") (pinfunction "3_3") (pintype "passive"))
    )
    (net (code "190") (name "unconnected-(JP19-Pad4)") (class "Default")
      (node (ref "JP19") (pin "4") (pinfunction "4_4") (pintype "passive"))
    )
    (net (code "191") (name "unconnected-(JP19-Pad5)") (class "Default")
      (node (ref "JP19") (pin "5") (pinfunction "5_5") (pintype "passive"))
    )
    (net (code "192") (name "unconnected-(JP19-Pad6)") (class "Default")
      (node (ref "JP19") (pin "6") (pinfunction "6_6") (pintype "passive"))
    )
    (net (code "193") (name "unconnected-(JP19-Pad7)") (class "Default")
      (node (ref "JP19") (pin "7") (pinfunction "7_7") (pintype "passive"))
    )
    (net (code "194") (name "unconnected-(JP19-Pad8)") (class "Default")
      (node (ref "JP19") (pin "8") (pinfunction "8_8") (pintype "passive"))
    )
    (net (code "195") (name "unconnected-(JP19-Pad9)") (class "Default")
      (node (ref "JP19") (pin "9") (pinfunction "9_9") (pintype "passive"))
    )
    (net (code "196") (name "unconnected-(JP19-Pad10)") (class "Default")
      (node (ref "JP19") (pin "10") (pinfunction "10_10") (pintype "passive"))
    )
    (net (code "197") (name "unconnected-(JP19-Pad11)") (class "Default")
      (node (ref "JP19") (pin "11") (pinfunction "11_11") (pintype "passive"))
    )
    (net (code "198") (name "unconnected-(JP19-Pad12)") (class "Default")
      (node (ref "JP19") (pin "12") (pinfunction "12_12") (pintype "passive"))
    )
    (net (code "199") (name "unconnected-(JP19-Pad13)") (class "Default")
      (node (ref "JP19") (pin "13") (pinfunction "13_13") (pintype "passive"))
    )
    (net (code "200") (name "unconnected-(JP19-Pad14)") (class "Default")
      (node (ref "JP19") (pin "14") (pinfunction "14_14") (pintype "passive"))
    )
    (net (code "201") (name "unconnected-(JP19-Pad15)") (class "Default")
      (node (ref "JP19") (pin "15") (pinfunction "15_15") (pintype "passive"))
    )
    (net (code "202") (name "unconnected-(S1-P1-Pad4)") (class "Default")
      (node (ref "S1") (pin "4") (pinfunction "P1_4") (pintype "passive"))
    )
    (net (code "203") (name "unconnected-(S1-S1-Pad2)") (class "Default")
      (node (ref "S1") (pin "2") (pinfunction "S1_2") (pintype "passive"))
    )
    (net (code "204") (name "unconnected-(S2-P1-Pad4)") (class "Default")
      (node (ref "S2") (pin "4") (pinfunction "P1_4") (pintype "passive"))
    )
    (net (code "205") (name "unconnected-(S2-S1-Pad2)") (class "Default")
      (node (ref "S2") (pin "2") (pinfunction "S1_2") (pintype "passive"))
    )
  )
)
